# OR_Gate.net
KiCad netlist of a schematic drawn in Altium Designer
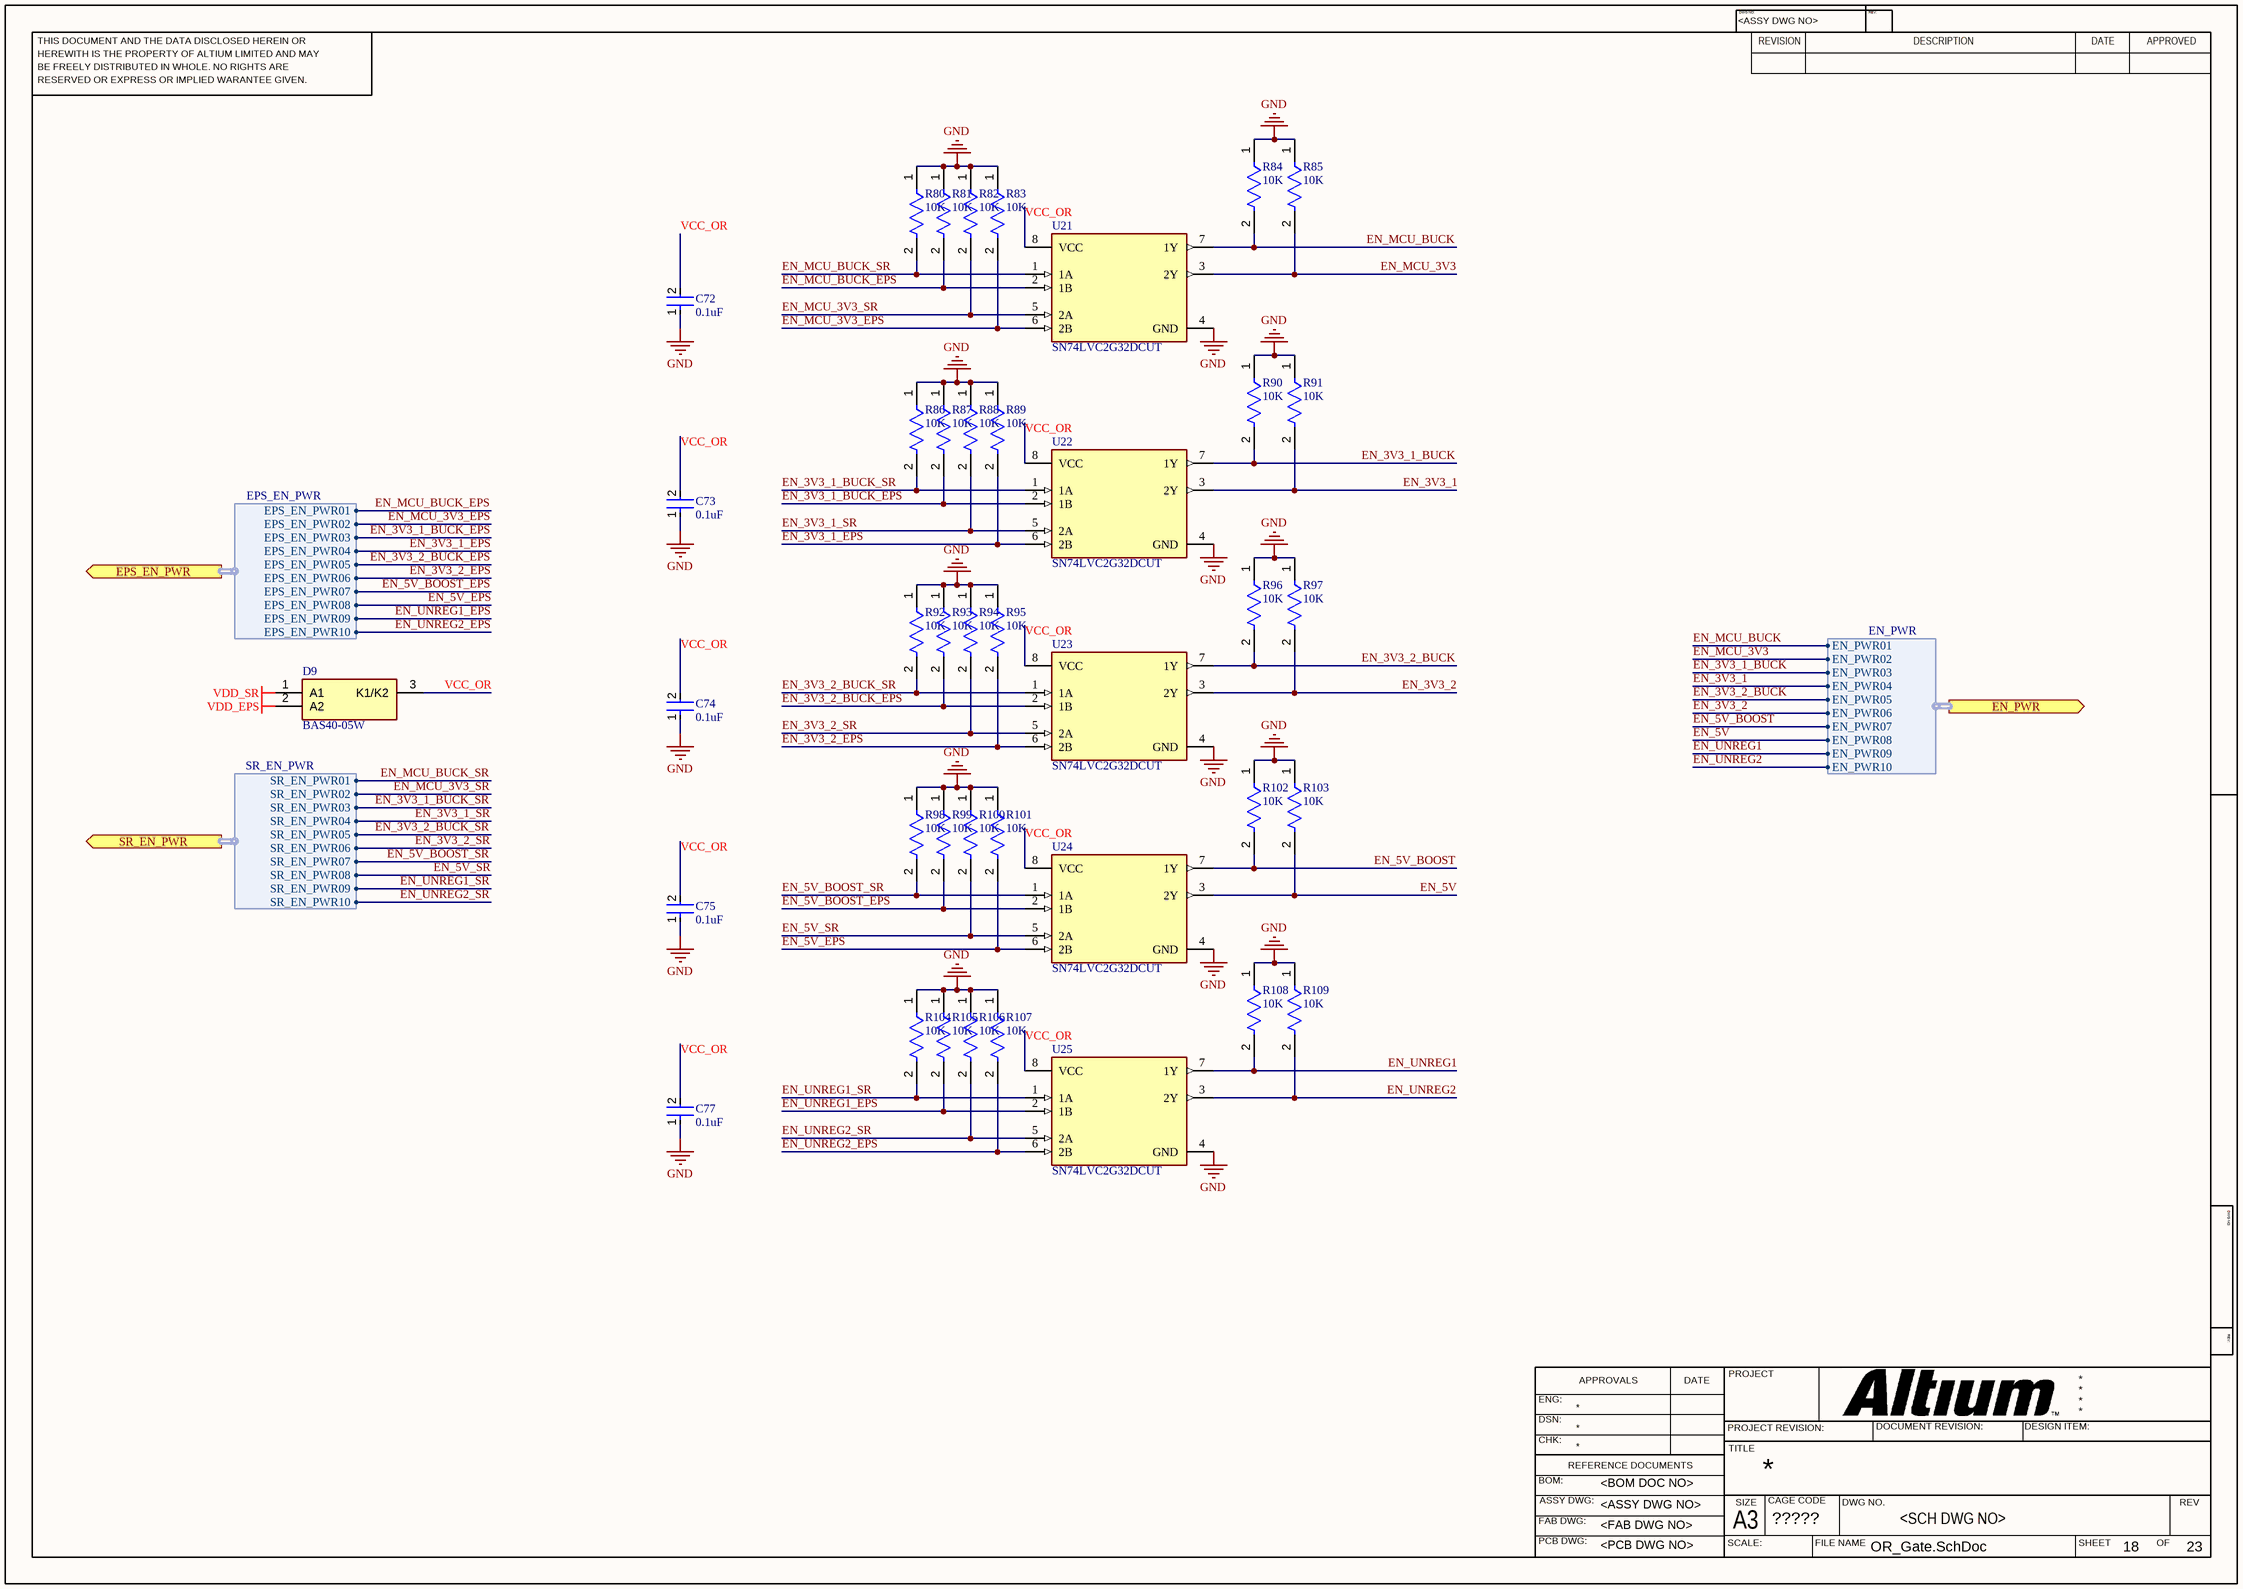
[diagram p0: OR_Gate.SchDoc]

(export (version "E")
  (design (tool "Eeschema 10.0.6"))
  (components
    (comp (ref "C72")
      (value "0.1uF")
      (footprint "FP-C0603C-CF-MFG")
      (description "CAP CER 0.1UF 50V X7R 0603")
      (fields (field (name "TOLERANCE") "0.1") (field (name "MANUFACTURER") "KEMET"))
      (libsource (lib "Altium Content Vault") (part "b4654b650e69147ec39a6b967a45e02"))
    )
    (comp (ref "C73")
      (value "0.1uF")
      (footprint "FP-C0603C-CF-MFG")
      (description "CAP CER 0.1UF 50V X7R 0603")
      (fields (field (name "TOLERANCE") "0.1") (field (name "MANUFACTURER") "KEMET"))
      (libsource (lib "Altium Content Vault") (part "b4654b650e69147ec39a6b967a45e02"))
    )
    (comp (ref "C74")
      (value "0.1uF")
      (footprint "FP-C0603C-CF-MFG")
      (description "CAP CER 0.1UF 50V X7R 0603")
      (fields (field (name "TOLERANCE") "0.1") (field (name "MANUFACTURER") "KEMET"))
      (libsource (lib "Altium Content Vault") (part "b4654b650e69147ec39a6b967a45e02"))
    )
    (comp (ref "C75")
      (value "0.1uF")
      (footprint "FP-C0603C-CF-MFG")
      (description "CAP CER 0.1UF 50V X7R 0603")
      (fields (field (name "TOLERANCE") "0.1") (field (name "MANUFACTURER") "KEMET"))
      (libsource (lib "Altium Content Vault") (part "b4654b650e69147ec39a6b967a45e02"))
    )
    (comp (ref "C77")
      (value "0.1uF")
      (footprint "FP-C0603C-CF-MFG")
      (description "CAP CER 0.1UF 50V X7R 0603")
      (fields (field (name "TOLERANCE") "0.1") (field (name "MANUFACTURER") "KEMET"))
      (libsource (lib "Altium Content Vault") (part "b4654b650e69147ec39a6b967a45e02"))
    )
    (comp (ref "D9")
      (value "BAS40-05W")
      (footprint "SamacSys:SOT65P210X110-3N")
      (description "Integrated Circuit")
      (libsource (lib "*") (part "BAS40-05W"))
    )
    (comp (ref "R80")
      (value "10K")
      (footprint "FP-RK73B1J-MFG")
      (description "RES 10K OHM 5% 1/10W 0603")
      (fields (field (name "TOLERANCE") "5%"))
      (libsource (lib "Altium Content Vault") (part "1029c3af85768c4190bb7ad29bc67b5"))
    )
    (comp (ref "R81")
      (value "10K")
      (footprint "FP-RK73B1J-MFG")
      (description "RES 10K OHM 5% 1/10W 0603")
      (fields (field (name "TOLERANCE") "5%"))
      (libsource (lib "Altium Content Vault") (part "1029c3af85768c4190bb7ad29bc67b5"))
    )
    (comp (ref "R82")
      (value "10K")
      (footprint "FP-RK73B1J-MFG")
      (description "RES 10K OHM 5% 1/10W 0603")
      (fields (field (name "TOLERANCE") "5%"))
      (libsource (lib "Altium Content Vault") (part "1029c3af85768c4190bb7ad29bc67b5"))
    )
    (comp (ref "R83")
      (value "10K")
      (footprint "FP-RK73B1J-MFG")
      (description "RES 10K OHM 5% 1/10W 0603")
      (fields (field (name "TOLERANCE") "5%"))
      (libsource (lib "Altium Content Vault") (part "1029c3af85768c4190bb7ad29bc67b5"))
    )
    (comp (ref "R84")
      (value "10K")
      (footprint "FP-RK73B1J-MFG")
      (description "RES 10K OHM 5% 1/10W 0603")
      (fields (field (name "TOLERANCE") "5%"))
      (libsource (lib "Altium Content Vault") (part "1029c3af85768c4190bb7ad29bc67b5"))
    )
    (comp (ref "R85")
      (value "10K")
      (footprint "FP-RK73B1J-MFG")
      (description "RES 10K OHM 5% 1/10W 0603")
      (fields (field (name "TOLERANCE") "5%"))
      (libsource (lib "Altium Content Vault") (part "1029c3af85768c4190bb7ad29bc67b5"))
    )
    (comp (ref "R86")
      (value "10K")
      (footprint "FP-RK73B1J-MFG")
      (description "RES 10K OHM 5% 1/10W 0603")
      (fields (field (name "TOLERANCE") "5%"))
      (libsource (lib "Altium Content Vault") (part "1029c3af85768c4190bb7ad29bc67b5"))
    )
    (comp (ref "R87")
      (value "10K")
      (footprint "FP-RK73B1J-MFG")
      (description "RES 10K OHM 5% 1/10W 0603")
      (fields (field (name "TOLERANCE") "5%"))
      (libsource (lib "Altium Content Vault") (part "1029c3af85768c4190bb7ad29bc67b5"))
    )
    (comp (ref "R88")
      (value "10K")
      (footprint "FP-RK73B1J-MFG")
      (description "RES 10K OHM 5% 1/10W 0603")
      (fields (field (name "TOLERANCE") "5%"))
      (libsource (lib "Altium Content Vault") (part "1029c3af85768c4190bb7ad29bc67b5"))
    )
    (comp (ref "R89")
      (value "10K")
      (footprint "FP-RK73B1J-MFG")
      (description "RES 10K OHM 5% 1/10W 0603")
      (fields (field (name "TOLERANCE") "5%"))
      (libsource (lib "Altium Content Vault") (part "1029c3af85768c4190bb7ad29bc67b5"))
    )
    (comp (ref "R90")
      (value "10K")
      (footprint "FP-RK73B1J-MFG")
      (description "RES 10K OHM 5% 1/10W 0603")
      (fields (field (name "TOLERANCE") "5%"))
      (libsource (lib "Altium Content Vault") (part "1029c3af85768c4190bb7ad29bc67b5"))
    )
    (comp (ref "R91")
      (value "10K")
      (footprint "FP-RK73B1J-MFG")
      (description "RES 10K OHM 5% 1/10W 0603")
      (fields (field (name "TOLERANCE") "5%"))
      (libsource (lib "Altium Content Vault") (part "1029c3af85768c4190bb7ad29bc67b5"))
    )
    (comp (ref "R92")
      (value "10K")
      (footprint "FP-RK73B1J-MFG")
      (description "RES 10K OHM 5% 1/10W 0603")
      (fields (field (name "TOLERANCE") "5%"))
      (libsource (lib "Altium Content Vault") (part "1029c3af85768c4190bb7ad29bc67b5"))
    )
    (comp (ref "R93")
      (value "10K")
      (footprint "FP-RK73B1J-MFG")
      (description "RES 10K OHM 5% 1/10W 0603")
      (fields (field (name "TOLERANCE") "5%"))
      (libsource (lib "Altium Content Vault") (part "1029c3af85768c4190bb7ad29bc67b5"))
    )
    (comp (ref "R94")
      (value "10K")
      (footprint "FP-RK73B1J-MFG")
      (description "RES 10K OHM 5% 1/10W 0603")
      (fields (field (name "TOLERANCE") "5%"))
      (libsource (lib "Altium Content Vault") (part "1029c3af85768c4190bb7ad29bc67b5"))
    )
    (comp (ref "R95")
      (value "10K")
      (footprint "FP-RK73B1J-MFG")
      (description "RES 10K OHM 5% 1/10W 0603")
      (fields (field (name "TOLERANCE") "5%"))
      (libsource (lib "Altium Content Vault") (part "1029c3af85768c4190bb7ad29bc67b5"))
    )
    (comp (ref "R96")
      (value "10K")
      (footprint "FP-RK73B1J-MFG")
      (description "RES 10K OHM 5% 1/10W 0603")
      (fields (field (name "TOLERANCE") "5%"))
      (libsource (lib "Altium Content Vault") (part "1029c3af85768c4190bb7ad29bc67b5"))
    )
    (comp (ref "R97")
      (value "10K")
      (footprint "FP-RK73B1J-MFG")
      (description "RES 10K OHM 5% 1/10W 0603")
      (fields (field (name "TOLERANCE") "5%"))
      (libsource (lib "Altium Content Vault") (part "1029c3af85768c4190bb7ad29bc67b5"))
    )
    (comp (ref "R98")
      (value "10K")
      (footprint "FP-RK73B1J-MFG")
      (description "RES 10K OHM 5% 1/10W 0603")
      (fields (field (name "TOLERANCE") "5%"))
      (libsource (lib "Altium Content Vault") (part "1029c3af85768c4190bb7ad29bc67b5"))
    )
    (comp (ref "R99")
      (value "10K")
      (footprint "FP-RK73B1J-MFG")
      (description "RES 10K OHM 5% 1/10W 0603")
      (fields (field (name "TOLERANCE") "5%"))
      (libsource (lib "Altium Content Vault") (part "1029c3af85768c4190bb7ad29bc67b5"))
    )
    (comp (ref "R100")
      (value "10K")
      (footprint "FP-RK73B1J-MFG")
      (description "RES 10K OHM 5% 1/10W 0603")
      (fields (field (name "TOLERANCE") "5%"))
      (libsource (lib "Altium Content Vault") (part "1029c3af85768c4190bb7ad29bc67b5"))
    )
    (comp (ref "R101")
      (value "10K")
      (footprint "FP-RK73B1J-MFG")
      (description "RES 10K OHM 5% 1/10W 0603")
      (fields (field (name "TOLERANCE") "5%"))
      (libsource (lib "Altium Content Vault") (part "1029c3af85768c4190bb7ad29bc67b5"))
    )
    (comp (ref "R102")
      (value "10K")
      (footprint "FP-RK73B1J-MFG")
      (description "RES 10K OHM 5% 1/10W 0603")
      (fields (field (name "TOLERANCE") "5%"))
      (libsource (lib "Altium Content Vault") (part "1029c3af85768c4190bb7ad29bc67b5"))
    )
    (comp (ref "R103")
      (value "10K")
      (footprint "FP-RK73B1J-MFG")
      (description "RES 10K OHM 5% 1/10W 0603")
      (fields (field (name "TOLERANCE") "5%"))
      (libsource (lib "Altium Content Vault") (part "1029c3af85768c4190bb7ad29bc67b5"))
    )
    (comp (ref "R104")
      (value "10K")
      (footprint "FP-RK73B1J-MFG")
      (description "RES 10K OHM 5% 1/10W 0603")
      (fields (field (name "TOLERANCE") "5%"))
      (libsource (lib "Altium Content Vault") (part "1029c3af85768c4190bb7ad29bc67b5"))
    )
    (comp (ref "R105")
      (value "10K")
      (footprint "FP-RK73B1J-MFG")
      (description "RES 10K OHM 5% 1/10W 0603")
      (fields (field (name "TOLERANCE") "5%"))
      (libsource (lib "Altium Content Vault") (part "1029c3af85768c4190bb7ad29bc67b5"))
    )
    (comp (ref "R106")
      (value "10K")
      (footprint "FP-RK73B1J-MFG")
      (description "RES 10K OHM 5% 1/10W 0603")
      (fields (field (name "TOLERANCE") "5%"))
      (libsource (lib "Altium Content Vault") (part "1029c3af85768c4190bb7ad29bc67b5"))
    )
    (comp (ref "R107")
      (value "10K")
      (footprint "FP-RK73B1J-MFG")
      (description "RES 10K OHM 5% 1/10W 0603")
      (fields (field (name "TOLERANCE") "5%"))
      (libsource (lib "Altium Content Vault") (part "1029c3af85768c4190bb7ad29bc67b5"))
    )
    (comp (ref "R108")
      (value "10K")
      (footprint "FP-RK73B1J-MFG")
      (description "RES 10K OHM 5% 1/10W 0603")
      (fields (field (name "TOLERANCE") "5%"))
      (libsource (lib "Altium Content Vault") (part "1029c3af85768c4190bb7ad29bc67b5"))
    )
    (comp (ref "R109")
      (value "10K")
      (footprint "FP-RK73B1J-MFG")
      (description "RES 10K OHM 5% 1/10W 0603")
      (fields (field (name "TOLERANCE") "5%"))
      (libsource (lib "Altium Content Vault") (part "1029c3af85768c4190bb7ad29bc67b5"))
    )
    (comp (ref "U21")
      (value "SN74LVC2G32DCUT")
      (footprint "FP-DCU0008A-IPC_B")
      (description "IC GATE OR 2CH 2-INP 8VSSOP")
      (libsource (lib "Altium Content Vault") (part "4205ed326eb504f488ab3427ef7e9a6"))
    )
    (comp (ref "U22")
      (value "SN74LVC2G32DCUT")
      (footprint "FP-DCU0008A-IPC_B")
      (description "IC GATE OR 2CH 2-INP 8VSSOP")
      (libsource (lib "Altium Content Vault") (part "4205ed326eb504f488ab3427ef7e9a6"))
    )
    (comp (ref "U23")
      (value "SN74LVC2G32DCUT")
      (footprint "FP-DCU0008A-IPC_B")
      (description "IC GATE OR 2CH 2-INP 8VSSOP")
      (libsource (lib "Altium Content Vault") (part "4205ed326eb504f488ab3427ef7e9a6"))
    )
    (comp (ref "U24")
      (value "SN74LVC2G32DCUT")
      (footprint "FP-DCU0008A-IPC_B")
      (description "IC GATE OR 2CH 2-INP 8VSSOP")
      (libsource (lib "Altium Content Vault") (part "4205ed326eb504f488ab3427ef7e9a6"))
    )
    (comp (ref "U25")
      (value "SN74LVC2G32DCUT")
      (footprint "FP-DCU0008A-IPC_B")
      (description "IC GATE OR 2CH 2-INP 8VSSOP")
      (libsource (lib "Altium Content Vault") (part "4205ed326eb504f488ab3427ef7e9a6"))
    )
  )
  (nets
    (net (code "4") (name "/EN_3V3_1") (class "Default")
      (node (ref "R91") (pin "2") (pinfunction "2_2") (pintype "passive"))
      (node (ref "U22") (pin "3") (pinfunction "2Y_3") (pintype "output"))
    )
    (net (code "5") (name "/EN_3V3_1_BUCK") (class "Default")
      (node (ref "R90") (pin "2") (pinfunction "2_2") (pintype "passive"))
      (node (ref "U22") (pin "7") (pinfunction "1Y_7") (pintype "output"))
    )
    (net (code "6") (name "/EN_3V3_1_BUCK_EPS") (class "Default")
      (node (ref "R87") (pin "2") (pinfunction "2_2") (pintype "passive"))
      (node (ref "U22") (pin "2") (pinfunction "1B_2") (pintype "input"))
    )
    (net (code "7") (name "/EN_3V3_1_BUCK_SR") (class "Default")
      (node (ref "R86") (pin "2") (pinfunction "2_2") (pintype "passive"))
      (node (ref "U22") (pin "1") (pinfunction "1A_1") (pintype "input"))
    )
    (net (code "8") (name "/EN_3V3_1_EPS") (class "Default")
      (node (ref "R89") (pin "2") (pinfunction "2_2") (pintype "passive"))
      (node (ref "U22") (pin "6") (pinfunction "2B_6") (pintype "input"))
    )
    (net (code "9") (name "/EN_3V3_1_SR") (class "Default")
      (node (ref "R88") (pin "2") (pinfunction "2_2") (pintype "passive"))
      (node (ref "U22") (pin "5") (pinfunction "2A_5") (pintype "input"))
    )
    (net (code "10") (name "/EN_3V3_2") (class "Default")
      (node (ref "R97") (pin "2") (pinfunction "2_2") (pintype "passive"))
      (node (ref "U23") (pin "3") (pinfunction "2Y_3") (pintype "output"))
    )
    (net (code "11") (name "/EN_3V3_2_BUCK") (class "Default")
      (node (ref "R96") (pin "2") (pinfunction "2_2") (pintype "passive"))
      (node (ref "U23") (pin "7") (pinfunction "1Y_7") (pintype "output"))
    )
    (net (code "12") (name "/EN_3V3_2_BUCK_EPS") (class "Default")
      (node (ref "R93") (pin "2") (pinfunction "2_2") (pintype "passive"))
      (node (ref "U23") (pin "2") (pinfunction "1B_2") (pintype "input"))
    )
    (net (code "13") (name "/EN_3V3_2_BUCK_SR") (class "Default")
      (node (ref "R92") (pin "2") (pinfunction "2_2") (pintype "passive"))
      (node (ref "U23") (pin "1") (pinfunction "1A_1") (pintype "input"))
    )
    (net (code "14") (name "/EN_3V3_2_EPS") (class "Default")
      (node (ref "R95") (pin "2") (pinfunction "2_2") (pintype "passive"))
      (node (ref "U23") (pin "6") (pinfunction "2B_6") (pintype "input"))
    )
    (net (code "15") (name "/EN_3V3_2_SR") (class "Default")
      (node (ref "R94") (pin "2") (pinfunction "2_2") (pintype "passive"))
      (node (ref "U23") (pin "5") (pinfunction "2A_5") (pintype "input"))
    )
    (net (code "16") (name "/EN_5V") (class "Default")
      (node (ref "R103") (pin "2") (pinfunction "2_2") (pintype "passive"))
      (node (ref "U24") (pin "3") (pinfunction "2Y_3") (pintype "output"))
    )
    (net (code "17") (name "/EN_5V_BOOST") (class "Default")
      (node (ref "R102") (pin "2") (pinfunction "2_2") (pintype "passive"))
      (node (ref "U24") (pin "7") (pinfunction "1Y_7") (pintype "output"))
    )
    (net (code "18") (name "/EN_5V_BOOST_EPS") (class "Default")
      (node (ref "R99") (pin "2") (pinfunction "2_2") (pintype "passive"))
      (node (ref "U24") (pin "2") (pinfunction "1B_2") (pintype "input"))
    )
    (net (code "19") (name "/EN_5V_BOOST_SR") (class "Default")
      (node (ref "R98") (pin "2") (pinfunction "2_2") (pintype "passive"))
      (node (ref "U24") (pin "1") (pinfunction "1A_1") (pintype "input"))
    )
    (net (code "20") (name "/EN_5V_EPS") (class "Default")
      (node (ref "R101") (pin "2") (pinfunction "2_2") (pintype "passive"))
      (node (ref "U24") (pin "6") (pinfunction "2B_6") (pintype "input"))
    )
    (net (code "21") (name "/EN_5V_SR") (class "Default")
      (node (ref "R100") (pin "2") (pinfunction "2_2") (pintype "passive"))
      (node (ref "U24") (pin "5") (pinfunction "2A_5") (pintype "input"))
    )
    (net (code "22") (name "/EN_MCU_3V3") (class "Default")
      (node (ref "R85") (pin "2") (pinfunction "2_2") (pintype "passive"))
      (node (ref "U21") (pin "3") (pinfunction "2Y_3") (pintype "output"))
    )
    (net (code "23") (name "/EN_MCU_3V3_EPS") (class "Default")
      (node (ref "R83") (pin "2") (pinfunction "2_2") (pintype "passive"))
      (node (ref "U21") (pin "6") (pinfunction "2B_6") (pintype "input"))
    )
    (net (code "24") (name "/EN_MCU_3V3_SR") (class "Default")
      (node (ref "R82") (pin "2") (pinfunction "2_2") (pintype "passive"))
      (node (ref "U21") (pin "5") (pinfunction "2A_5") (pintype "input"))
    )
    (net (code "25") (name "/EN_MCU_BUCK") (class "Default")
      (node (ref "R84") (pin "2") (pinfunction "2_2") (pintype "passive"))
      (node (ref "U21") (pin "7") (pinfunction "1Y_7") (pintype "output"))
    )
    (net (code "26") (name "/EN_MCU_BUCK_EPS") (class "Default")
      (node (ref "R81") (pin "2") (pinfunction "2_2") (pintype "passive"))
      (node (ref "U21") (pin "2") (pinfunction "1B_2") (pintype "input"))
    )
    (net (code "27") (name "/EN_MCU_BUCK_SR") (class "Default")
      (node (ref "R80") (pin "2") (pinfunction "2_2") (pintype "passive"))
      (node (ref "U21") (pin "1") (pinfunction "1A_1") (pintype "input"))
    )
    (net (code "28") (name "/EN_UNREG1") (class "Default")
      (node (ref "R108") (pin "2") (pinfunction "2_2") (pintype "passive"))
      (node (ref "U25") (pin "7") (pinfunction "1Y_7") (pintype "output"))
    )
    (net (code "29") (name "/EN_UNREG1_EPS") (class "Default")
      (node (ref "R105") (pin "2") (pinfunction "2_2") (pintype "passive"))
      (node (ref "U25") (pin "2") (pinfunction "1B_2") (pintype "input"))
    )
    (net (code "30") (name "/EN_UNREG1_SR") (class "Default")
      (node (ref "R104") (pin "2") (pinfunction "2_2") (pintype "passive"))
      (node (ref "U25") (pin "1") (pinfunction "1A_1") (pintype "input"))
    )
    (net (code "31") (name "/EN_UNREG2") (class "Default")
      (node (ref "R109") (pin "2") (pinfunction "2_2") (pintype "passive"))
      (node (ref "U25") (pin "3") (pinfunction "2Y_3") (pintype "output"))
    )
    (net (code "32") (name "/EN_UNREG2_EPS") (class "Default")
      (node (ref "R107") (pin "2") (pinfunction "2_2") (pintype "passive"))
      (node (ref "U25") (pin "6") (pinfunction "2B_6") (pintype "input"))
    )
    (net (code "33") (name "/EN_UNREG2_SR") (class "Default")
      (node (ref "R106") (pin "2") (pinfunction "2_2") (pintype "passive"))
      (node (ref "U25") (pin "5") (pinfunction "2A_5") (pintype "input"))
    )
    (net (code "34") (name "/VCC_OR") (class "Default")
      (node (ref "C72") (pin "2") (pinfunction "2_2") (pintype "passive"))
      (node (ref "C73") (pin "2") (pinfunction "2_2") (pintype "passive"))
      (node (ref "C74") (pin "2") (pinfunction "2_2") (pintype "passive"))
      (node (ref "C75") (pin "2") (pinfunction "2_2") (pintype "passive"))
      (node (ref "C77") (pin "2") (pinfunction "2_2") (pintype "passive"))
      (node (ref "D9") (pin "3") (pinfunction "K1/K2_3") (pintype "passive"))
      (node (ref "U21") (pin "8") (pinfunction "VCC_8") (pintype "power_in"))
      (node (ref "U22") (pin "8") (pinfunction "VCC_8") (pintype "power_in"))
      (node (ref "U23") (pin "8") (pinfunction "VCC_8") (pintype "power_in"))
      (node (ref "U24") (pin "8") (pinfunction "VCC_8") (pintype "power_in"))
      (node (ref "U25") (pin "8") (pinfunction "VCC_8") (pintype "power_in"))
    )
    (net (code "38") (name "GND") (class "Default")
      (node (ref "C72") (pin "1") (pinfunction "1_1") (pintype "passive"))
      (node (ref "C73") (pin "1") (pinfunction "1_1") (pintype "passive"))
      (node (ref "C74") (pin "1") (pinfunction "1_1") (pintype "passive"))
      (node (ref "C75") (pin "1") (pinfunction "1_1") (pintype "passive"))
      (node (ref "C77") (pin "1") (pinfunction "1_1") (pintype "passive"))
      (node (ref "R100") (pin "1") (pinfunction "1_1") (pintype "passive"))
      (node (ref "R101") (pin "1") (pinfunction "1_1") (pintype "passive"))
      (node (ref "R102") (pin "1") (pinfunction "1_1") (pintype "passive"))
      (node (ref "R103") (pin "1") (pinfunction "1_1") (pintype "passive"))
      (node (ref "R104") (pin "1") (pinfunction "1_1") (pintype "passive"))
      (node (ref "R105") (pin "1") (pinfunction "1_1") (pintype "passive"))
      (node (ref "R106") (pin "1") (pinfunction "1_1") (pintype "passive"))
      (node (ref "R107") (pin "1") (pinfunction "1_1") (pintype "passive"))
      (node (ref "R108") (pin "1") (pinfunction "1_1") (pintype "passive"))
      (node (ref "R109") (pin "1") (pinfunction "1_1") (pintype "passive"))
      (node (ref "R80") (pin "1") (pinfunction "1_1") (pintype "passive"))
      (node (ref "R81") (pin "1") (pinfunction "1_1") (pintype "passive"))
      (node (ref "R82") (pin "1") (pinfunction "1_1") (pintype "passive"))
      (node (ref "R83") (pin "1") (pinfunction "1_1") (pintype "passive"))
      (node (ref "R84") (pin "1") (pinfunction "1_1") (pintype "passive"))
      (node (ref "R85") (pin "1") (pinfunction "1_1") (pintype "passive"))
      (node (ref "R86") (pin "1") (pinfunction "1_1") (pintype "passive"))
      (node (ref "R87") (pin "1") (pinfunction "1_1") (pintype "passive"))
      (node (ref "R88") (pin "1") (pinfunction "1_1") (pintype "passive"))
      (node (ref "R89") (pin "1") (pinfunction "1_1") (pintype "passive"))
      (node (ref "R90") (pin "1") (pinfunction "1_1") (pintype "passive"))
      (node (ref "R91") (pin "1") (pinfunction "1_1") (pintype "passive"))
      (node (ref "R92") (pin "1") (pinfunction "1_1") (pintype "passive"))
      (node (ref "R93") (pin "1") (pinfunction "1_1") (pintype "passive"))
      (node (ref "R94") (pin "1") (pinfunction "1_1") (pintype "passive"))
      (node (ref "R95") (pin "1") (pinfunction "1_1") (pintype "passive"))
      (node (ref "R96") (pin "1") (pinfunction "1_1") (pintype "passive"))
      (node (ref "R97") (pin "1") (pinfunction "1_1") (pintype "passive"))
      (node (ref "R98") (pin "1") (pinfunction "1_1") (pintype "passive"))
      (node (ref "R99") (pin "1") (pinfunction "1_1") (pintype "passive"))
      (node (ref "U21") (pin "4") (pinfunction "GND_4") (pintype "power_in"))
      (node (ref "U22") (pin "4") (pinfunction "GND_4") (pintype "power_in"))
      (node (ref "U23") (pin "4") (pinfunction "GND_4") (pintype "power_in"))
      (node (ref "U24") (pin "4") (pinfunction "GND_4") (pintype "power_in"))
      (node (ref "U25") (pin "4") (pinfunction "GND_4") (pintype "power_in"))
    )
    (net (code "39") (name "VDD_EPS") (class "Default")
      (node (ref "D9") (pin "2") (pinfunction "A2_2") (pintype "passive"))
    )
    (net (code "40") (name "VDD_SR") (class "Default")
      (node (ref "D9") (pin "1") (pinfunction "A1_1") (pintype "passive"))
    )
  )
)
